# main.net
KiCad netlist of a schematic drawn in Altium Designer
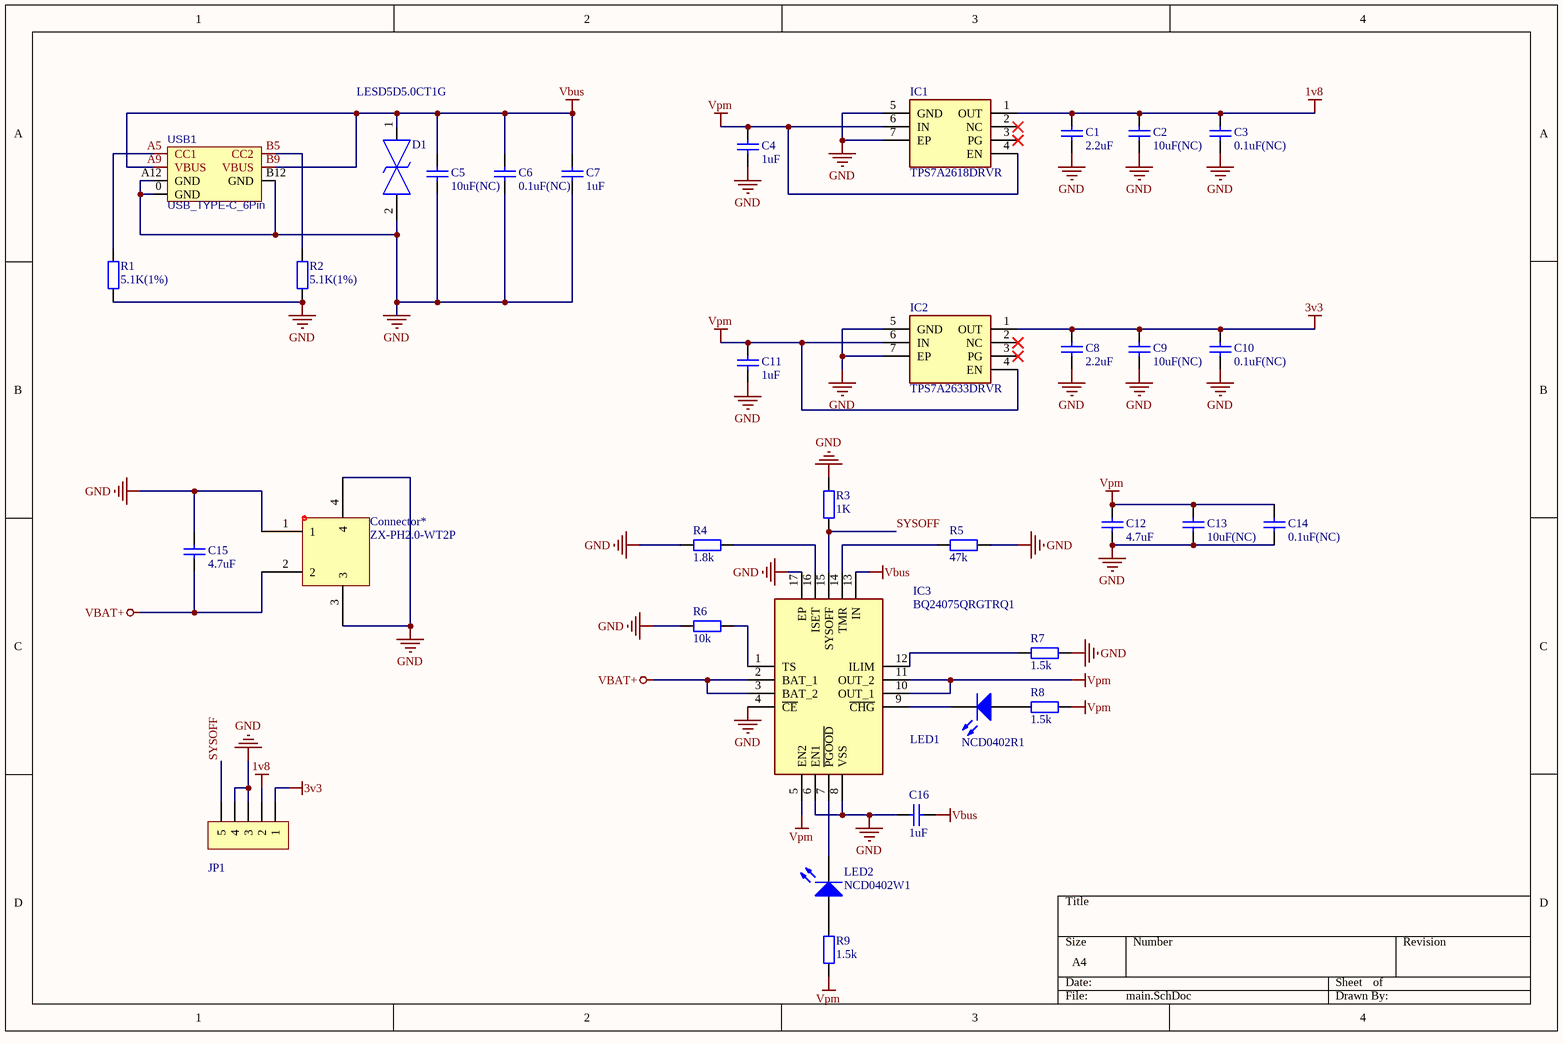
[diagram p0: main.SchDoc]

(export (version "E")
  (design (tool "Eeschema 10.0.6"))
  (components
    (comp (ref "C1")
      (value "2.2uF")
      (footprint "C0402_L")
      (description "贴片电容/MLCC电容")
      (libsource (lib "0.1 - 电阻-电容-电感-保险丝-晶振-晶体-磁珠-电位器-法拉电容-馈通电容") (part "C"))
    )
    (comp (ref "C2")
      (value "10uF(NC)")
      (footprint "C0402_L")
      (description "贴片电容/MLCC电容")
      (libsource (lib "0.1 - 电阻-电容-电感-保险丝-晶振-晶体-磁珠-电位器-法拉电容-馈通电容") (part "C"))
    )
    (comp (ref "C3")
      (value "0.1uF(NC)")
      (footprint "C0402_L")
      (description "贴片电容/MLCC电容")
      (libsource (lib "0.1 - 电阻-电容-电感-保险丝-晶振-晶体-磁珠-电位器-法拉电容-馈通电容") (part "C"))
    )
    (comp (ref "C4")
      (value "1uF")
      (footprint "C0402_L")
      (description "贴片电容/MLCC电容")
      (libsource (lib "0.1 - 电阻-电容-电感-保险丝-晶振-晶体-磁珠-电位器-法拉电容-馈通电容") (part "C"))
    )
    (comp (ref "C5")
      (value "10uF(NC)")
      (footprint "C0402_L")
      (description "贴片电容/MLCC电容")
      (libsource (lib "0.1 - 电阻-电容-电感-保险丝-晶振-晶体-磁珠-电位器-法拉电容-馈通电容") (part "C"))
    )
    (comp (ref "C6")
      (value "0.1uF(NC)")
      (footprint "C0402_L")
      (description "贴片电容/MLCC电容")
      (libsource (lib "0.1 - 电阻-电容-电感-保险丝-晶振-晶体-磁珠-电位器-法拉电容-馈通电容") (part "C"))
    )
    (comp (ref "C7")
      (value "1uF")
      (footprint "C0402_L")
      (description "贴片电容/MLCC电容")
      (libsource (lib "0.1 - 电阻-电容-电感-保险丝-晶振-晶体-磁珠-电位器-法拉电容-馈通电容") (part "C"))
    )
    (comp (ref "C8")
      (value "2.2uF")
      (footprint "C0402_L")
      (description "贴片电容/MLCC电容")
      (libsource (lib "0.1 - 电阻-电容-电感-保险丝-晶振-晶体-磁珠-电位器-法拉电容-馈通电容") (part "C"))
    )
    (comp (ref "C9")
      (value "10uF(NC)")
      (footprint "C0402_L")
      (description "贴片电容/MLCC电容")
      (libsource (lib "0.1 - 电阻-电容-电感-保险丝-晶振-晶体-磁珠-电位器-法拉电容-馈通电容") (part "C"))
    )
    (comp (ref "C10")
      (value "0.1uF(NC)")
      (footprint "C0402_L")
      (description "贴片电容/MLCC电容")
      (libsource (lib "0.1 - 电阻-电容-电感-保险丝-晶振-晶体-磁珠-电位器-法拉电容-馈通电容") (part "C"))
    )
    (comp (ref "C11")
      (value "1uF")
      (footprint "C0402_L")
      (description "贴片电容/MLCC电容")
      (libsource (lib "0.1 - 电阻-电容-电感-保险丝-晶振-晶体-磁珠-电位器-法拉电容-馈通电容") (part "C"))
    )
    (comp (ref "C12")
      (value "4.7uF")
      (footprint "C0402_L")
      (description "贴片电容/MLCC电容")
      (libsource (lib "0.1 - 电阻-电容-电感-保险丝-晶振-晶体-磁珠-电位器-法拉电容-馈通电容") (part "C"))
    )
    (comp (ref "C13")
      (value "10uF(NC)")
      (footprint "C0402_L")
      (description "贴片电容/MLCC电容")
      (libsource (lib "0.1 - 电阻-电容-电感-保险丝-晶振-晶体-磁珠-电位器-法拉电容-馈通电容") (part "C"))
    )
    (comp (ref "C14")
      (value "0.1uF(NC)")
      (footprint "C0402_L")
      (description "贴片电容/MLCC电容")
      (libsource (lib "0.1 - 电阻-电容-电感-保险丝-晶振-晶体-磁珠-电位器-法拉电容-馈通电容") (part "C"))
    )
    (comp (ref "C15")
      (value "4.7uF")
      (footprint "C0402_L")
      (description "贴片电容/MLCC电容")
      (libsource (lib "0.1 - 电阻-电容-电感-保险丝-晶振-晶体-磁珠-电位器-法拉电容-馈通电容") (part "C"))
    )
    (comp (ref "C16")
      (value "1uF")
      (footprint "C0402_L")
      (description "贴片电容/MLCC电容")
      (libsource (lib "0.1 - 电阻-电容-电感-保险丝-晶振-晶体-磁珠-电位器-法拉电容-馈通电容") (part "C"))
    )
    (comp (ref "Connector*")
      (value "ZX-PH2.0-WT2P")
      (footprint "ZX-PH2.0-WT2P")
      (description "https://jlcpcb.com/partdetail/Megastar-ZX_PH2_0WT2P/C7429689")
      (libsource (lib "myConnectors") (part "ZX-PH2.0-WT2P"))
    )
    (comp (ref "D1")
      (value "LESD5D5.0CT1G")
      (footprint "SamacSys:LESD5D50CT1G")
      (description "TVS Diode (Bi-directional)")
      (libsource (lib "*") (part "LESD5D5.0CT1G"))
    )
    (comp (ref "IC1")
      (value "TPS7A2618DRVR")
      (footprint "SamacSys:TPS7A2633DRVR")
      (description "Integrated Circuit")
      (fields
        (field (name "MANUFACTURER_PART_NUMBER") "TPS7A2633DRVR")
        (field (name "MOUSER PART NUMBER") "595-TPS7A2633DRVR")
      )
      (libsource (lib "*") (part "TPS7A2633DRVR"))
    )
    (comp (ref "IC2")
      (value "TPS7A2633DRVR")
      (footprint "SamacSys:TPS7A2633DRVR")
      (description "Integrated Circuit")
      (fields (field (name "MOUSER PART NUMBER") "595-TPS7A2633DRVR"))
      (libsource (lib "*") (part "TPS7A2633DRVR"))
    )
    (comp (ref "IC3")
      (value "BQ24075QRGTRQ1")
      (footprint "SamacSys:QFN50P300X300X100-17N-D")
      (description "Integrated Circuit")
      (fields (field (name "MOUSER PART NUMBER") "595-BQ24075QRGTRQ1"))
      (libsource (lib "*") (part "BQ24075QRGTRQ1"))
    )
    (comp (ref "JP1")
      (value "HDR-1X5")
      (footprint "HDR2.54-LI-5P")
      (description "5P接插件")
      (libsource (lib "5.5 - 2.54mm连接器(KF2EDGK_XH2.54_2.54排针排母)") (part "Header 5"))
    )
    (comp (ref "LED1")
      (value "NCD0402R1")
      (footprint "LED0402_R")
      (libsource (lib "0.3 - LED发光二极管-IR二极管_接收管-光耦") (part "LED"))
    )
    (comp (ref "LED2")
      (value "NCD0402W1")
      (footprint "LED0402_W")
      (libsource (lib "0.3 - LED发光二极管-IR二极管_接收管-光耦") (part "LED"))
    )
    (comp (ref "R1")
      (value "5.1K(1%)")
      (footprint "R0402_L")
      (description "贴片电阻")
      (libsource (lib "0.1 - 电阻-电容-电感-保险丝-晶振-晶体-磁珠-电位器-法拉电容-馈通电容") (part "R"))
    )
    (comp (ref "R2")
      (value "5.1K(1%)")
      (footprint "R0402_L")
      (description "贴片电阻")
      (libsource (lib "0.1 - 电阻-电容-电感-保险丝-晶振-晶体-磁珠-电位器-法拉电容-馈通电容") (part "R"))
    )
    (comp (ref "R3")
      (value "1K")
      (footprint "R0402_L")
      (description "贴片电阻")
      (libsource (lib "0.1 - 电阻-电容-电感-保险丝-晶振-晶体-磁珠-电位器-法拉电容-馈通电容") (part "R"))
    )
    (comp (ref "R4")
      (value "1.8k")
      (footprint "R0402_L")
      (description "RISET = 890 AΩ / 0.5A = 1.8k")
      (libsource (lib "0.1 - 电阻-电容-电感-保险丝-晶振-晶体-磁珠-电位器-法拉电容-馈通电容") (part "R"))
    )
    (comp (ref "R5")
      (value "47k")
      (footprint "R0402_L")
      (libsource (lib "0.1 - 电阻-电容-电感-保险丝-晶振-晶体-磁珠-电位器-法拉电容-馈通电容") (part "R"))
    )
    (comp (ref "R6")
      (value "10k")
      (footprint "R0402_L")
      (description "贴片电阻")
      (libsource (lib "0.1 - 电阻-电容-电感-保险丝-晶振-晶体-磁珠-电位器-法拉电容-馈通电容") (part "R"))
    )
    (comp (ref "R7")
      (value "1.5k")
      (footprint "R0402_L")
      (description "1.5k 1A limitation of input\r\n\r\nRISET = 1550 AΩ / 1 A = 1.5k")
      (libsource (lib "0.1 - 电阻-电容-电感-保险丝-晶振-晶体-磁珠-电位器-法拉电容-馈通电容") (part "R"))
    )
    (comp (ref "R8")
      (value "1.5k")
      (footprint "R0402_L")
      (description "贴片电阻")
      (libsource (lib "0.1 - 电阻-电容-电感-保险丝-晶振-晶体-磁珠-电位器-法拉电容-馈通电容") (part "R"))
    )
    (comp (ref "R9")
      (value "1.5k")
      (footprint "R0402_L")
      (description "贴片电阻")
      (libsource (lib "0.1 - 电阻-电容-电感-保险丝-晶振-晶体-磁珠-电位器-法拉电容-馈通电容") (part "R"))
    )
    (comp (ref "USB1")
      (value "USB_TYPE-C_6Pin")
      (footprint "USB-C-SMD_6P")
      (description "USB_TYPE-C_6Pin母座")
      (libsource (lib "0.6 - 电源_音频_USB Type-C_HDMI_XT60_5557_D-SUB_RJ45_SD-TF_SIM插座") (part "USB_TYPE-C_6Pin"))
    )
  )
  (nets
    (net (code "1") (name "/SYSOFF") (class "Default")
      (node (ref "IC3") (pin "15") (pinfunction "SYSOFF_15") (pintype "passive"))
      (node (ref "JP1") (pin "5") (pinfunction "5_5") (pintype "passive"))
      (node (ref "R3") (pin "2") (pinfunction "2_2") (pintype "passive"))
    )
    (net (code "2") (name "1v8") (class "Default")
      (node (ref "C1") (pin "1") (pinfunction "1_1") (pintype "passive"))
      (node (ref "C2") (pin "1") (pinfunction "1_1") (pintype "passive"))
      (node (ref "C3") (pin "1") (pinfunction "1_1") (pintype "passive"))
      (node (ref "IC1") (pin "1") (pinfunction "OUT_1") (pintype "passive"))
      (node (ref "JP1") (pin "2") (pinfunction "2_2") (pintype "passive"))
    )
    (net (code "3") (name "3v3") (class "Default")
      (node (ref "C10") (pin "1") (pinfunction "1_1") (pintype "passive"))
      (node (ref "C8") (pin "1") (pinfunction "1_1") (pintype "passive"))
      (node (ref "C9") (pin "1") (pinfunction "1_1") (pintype "passive"))
      (node (ref "IC2") (pin "1") (pinfunction "OUT_1") (pintype "passive"))
      (node (ref "JP1") (pin "1") (pinfunction "1_1") (pintype "passive"))
    )
    (net (code "4") (name "GND") (class "Default")
      (node (ref "C1") (pin "2") (pinfunction "2_2") (pintype "passive"))
      (node (ref "C10") (pin "2") (pinfunction "2_2") (pintype "passive"))
      (node (ref "C11") (pin "2") (pinfunction "2_2") (pintype "passive"))
      (node (ref "C12") (pin "2") (pinfunction "2_2") (pintype "passive"))
      (node (ref "C13") (pin "2") (pinfunction "2_2") (pintype "passive"))
      (node (ref "C14") (pin "2") (pinfunction "2_2") (pintype "passive"))
      (node (ref "C15") (pin "1") (pinfunction "1_1") (pintype "passive"))
      (node (ref "C16") (pin "2") (pinfunction "2_2") (pintype "passive"))
      (node (ref "C2") (pin "2") (pinfunction "2_2") (pintype "passive"))
      (node (ref "C3") (pin "2") (pinfunction "2_2") (pintype "passive"))
      (node (ref "C4") (pin "2") (pinfunction "2_2") (pintype "passive"))
      (node (ref "C5") (pin "2") (pinfunction "2_2") (pintype "passive"))
      (node (ref "C6") (pin "1") (pinfunction "1_1") (pintype "passive"))
      (node (ref "C7") (pin "2") (pinfunction "2_2") (pintype "passive"))
      (node (ref "C8") (pin "2") (pinfunction "2_2") (pintype "passive"))
      (node (ref "C9") (pin "2") (pinfunction "2_2") (pintype "passive"))
      (node (ref "Connector*") (pin "1") (pinfunction "1_1") (pintype "passive"))
      (node (ref "Connector*") (pin "3") (pinfunction "3_3") (pintype "passive"))
      (node (ref "Connector*") (pin "4") (pinfunction "4_4") (pintype "passive"))
      (node (ref "D1") (pin "2") (pinfunction "2_2") (pintype "passive"))
      (node (ref "IC1") (pin "5") (pinfunction "GND_5") (pintype "passive"))
      (node (ref "IC1") (pin "7") (pinfunction "EP_7") (pintype "passive"))
      (node (ref "IC2") (pin "5") (pinfunction "GND_5") (pintype "passive"))
      (node (ref "IC2") (pin "7") (pinfunction "EP_7") (pintype "passive"))
      (node (ref "IC3") (pin "17") (pinfunction "EP_17") (pintype "passive"))
      (node (ref "IC3") (pin "4") (pinfunction "~{CE}_4") (pintype "passive"))
      (node (ref "IC3") (pin "6") (pinfunction "EN1_6") (pintype "passive"))
      (node (ref "IC3") (pin "8") (pinfunction "VSS_8") (pintype "passive"))
      (node (ref "JP1") (pin "3") (pinfunction "3_3") (pintype "passive"))
      (node (ref "JP1") (pin "4") (pinfunction "4_4") (pintype "passive"))
      (node (ref "R1") (pin "1") (pinfunction "1_1") (pintype "passive"))
      (node (ref "R2") (pin "1") (pinfunction "1_1") (pintype "passive"))
      (node (ref "R3") (pin "1") (pinfunction "1_1") (pintype "passive"))
      (node (ref "R4") (pin "2") (pinfunction "2_2") (pintype "passive"))
      (node (ref "R5") (pin "1") (pinfunction "1_1") (pintype "passive"))
      (node (ref "R6") (pin "2") (pinfunction "2_2") (pintype "passive"))
      (node (ref "R7") (pin "1") (pinfunction "1_1") (pintype "passive"))
      (node (ref "USB1") (pin "0") (pinfunction "GND_0") (pintype "passive"))
      (node (ref "USB1") (pin "A12") (pinfunction "GND_A12") (pintype "passive"))
      (node (ref "USB1") (pin "B12") (pinfunction "GND_B12") (pintype "passive"))
    )
    (net (code "5") (name "Net-(IC3-ILIM)") (class "Default")
      (node (ref "IC3") (pin "12") (pinfunction "ILIM_12") (pintype "passive"))
      (node (ref "R7") (pin "2") (pinfunction "2_2") (pintype "passive"))
    )
    (net (code "6") (name "Net-(IC3-ISET)") (class "Default")
      (node (ref "IC3") (pin "16") (pinfunction "ISET_16") (pintype "passive"))
      (node (ref "R4") (pin "1") (pinfunction "1_1") (pintype "passive"))
    )
    (net (code "7") (name "Net-(IC3-TMR)") (class "Default")
      (node (ref "IC3") (pin "14") (pinfunction "TMR_14") (pintype "passive"))
      (node (ref "R5") (pin "2") (pinfunction "2_2") (pintype "passive"))
    )
    (net (code "8") (name "Net-(IC3-TS)") (class "Default")
      (node (ref "IC3") (pin "1") (pinfunction "TS_1") (pintype "passive"))
      (node (ref "R6") (pin "1") (pinfunction "1_1") (pintype "passive"))
    )
    (net (code "9") (name "Net-(IC3-~{CHG})") (class "Default")
      (node (ref "IC3") (pin "9") (pinfunction "~{CHG}_9") (pintype "passive"))
      (node (ref "LED1") (pin "2") (pinfunction "K_2") (pintype "passive"))
    )
    (net (code "10") (name "Net-(IC3-~{PGOOD})") (class "Default")
      (node (ref "IC3") (pin "7") (pinfunction "~{PGOOD}_7") (pintype "passive"))
      (node (ref "LED2") (pin "2") (pinfunction "K_2") (pintype "passive"))
    )
    (net (code "11") (name "Net-(LED1-A)") (class "Default")
      (node (ref "LED1") (pin "1") (pinfunction "A_1") (pintype "passive"))
      (node (ref "R8") (pin "2") (pinfunction "2_2") (pintype "passive"))
    )
    (net (code "12") (name "Net-(LED2-A)") (class "Default")
      (node (ref "LED2") (pin "1") (pinfunction "A_1") (pintype "passive"))
      (node (ref "R9") (pin "2") (pinfunction "2_2") (pintype "passive"))
    )
    (net (code "13") (name "Net-(USB1-CC1)") (class "Default")
      (node (ref "R1") (pin "2") (pinfunction "2_2") (pintype "passive"))
      (node (ref "USB1") (pin "A5") (pinfunction "CC1_A5") (pintype "passive"))
    )
    (net (code "14") (name "Net-(USB1-CC2)") (class "Default")
      (node (ref "R2") (pin "2") (pinfunction "2_2") (pintype "passive"))
      (node (ref "USB1") (pin "B5") (pinfunction "CC2_B5") (pintype "passive"))
    )
    (net (code "15") (name "VBAT+") (class "Default")
      (node (ref "C15") (pin "2") (pinfunction "2_2") (pintype "passive"))
      (node (ref "Connector*") (pin "2") (pinfunction "2_2") (pintype "passive"))
      (node (ref "IC3") (pin "2") (pinfunction "BAT_1_2") (pintype "passive"))
      (node (ref "IC3") (pin "3") (pinfunction "BAT_2_3") (pintype "passive"))
    )
    (net (code "16") (name "Vbus") (class "Default")
      (node (ref "C16") (pin "1") (pinfunction "1_1") (pintype "passive"))
      (node (ref "C5") (pin "1") (pinfunction "1_1") (pintype "passive"))
      (node (ref "C6") (pin "2") (pinfunction "2_2") (pintype "passive"))
      (node (ref "C7") (pin "1") (pinfunction "1_1") (pintype "passive"))
      (node (ref "D1") (pin "1") (pinfunction "1_1") (pintype "passive"))
      (node (ref "IC3") (pin "13") (pinfunction "IN_13") (pintype "passive"))
      (node (ref "USB1") (pin "A9") (pinfunction "VBUS_A9") (pintype "passive"))
      (node (ref "USB1") (pin "B9") (pinfunction "VBUS_B9") (pintype "passive"))
    )
    (net (code "17") (name "Vpm") (class "Default")
      (node (ref "C11") (pin "1") (pinfunction "1_1") (pintype "passive"))
      (node (ref "C12") (pin "1") (pinfunction "1_1") (pintype "passive"))
      (node (ref "C13") (pin "1") (pinfunction "1_1") (pintype "passive"))
      (node (ref "C14") (pin "1") (pinfunction "1_1") (pintype "passive"))
      (node (ref "C4") (pin "1") (pinfunction "1_1") (pintype "passive"))
      (node (ref "IC1") (pin "4") (pinfunction "EN_4") (pintype "passive"))
      (node (ref "IC1") (pin "6") (pinfunction "IN_6") (pintype "passive"))
      (node (ref "IC2") (pin "4") (pinfunction "EN_4") (pintype "passive"))
      (node (ref "IC2") (pin "6") (pinfunction "IN_6") (pintype "passive"))
      (node (ref "IC3") (pin "10") (pinfunction "OUT_1_10") (pintype "passive"))
      (node (ref "IC3") (pin "11") (pinfunction "OUT_2_11") (pintype "passive"))
      (node (ref "IC3") (pin "5") (pinfunction "EN2_5") (pintype "passive"))
      (node (ref "R8") (pin "1") (pinfunction "1_1") (pintype "passive"))
      (node (ref "R9") (pin "1") (pinfunction "1_1") (pintype "passive"))
    )
    (net (code "18") (name "unconnected-(IC1-NC-Pad2)") (class "Default")
      (node (ref "IC1") (pin "2") (pinfunction "NC_2") (pintype "passive+no_connect"))
    )
    (net (code "19") (name "unconnected-(IC1-PG-Pad3)") (class "Default")
      (node (ref "IC1") (pin "3") (pinfunction "PG_3") (pintype "passive+no_connect"))
    )
    (net (code "20") (name "unconnected-(IC2-NC-Pad2)") (class "Default")
      (node (ref "IC2") (pin "2") (pinfunction "NC_2") (pintype "passive+no_connect"))
    )
    (net (code "21") (name "unconnected-(IC2-PG-Pad3)") (class "Default")
      (node (ref "IC2") (pin "3") (pinfunction "PG_3") (pintype "passive+no_connect"))
    )
  )
)
